# sapflow_v4.net
KiCad netlist of a schematic drawn in EAGLE
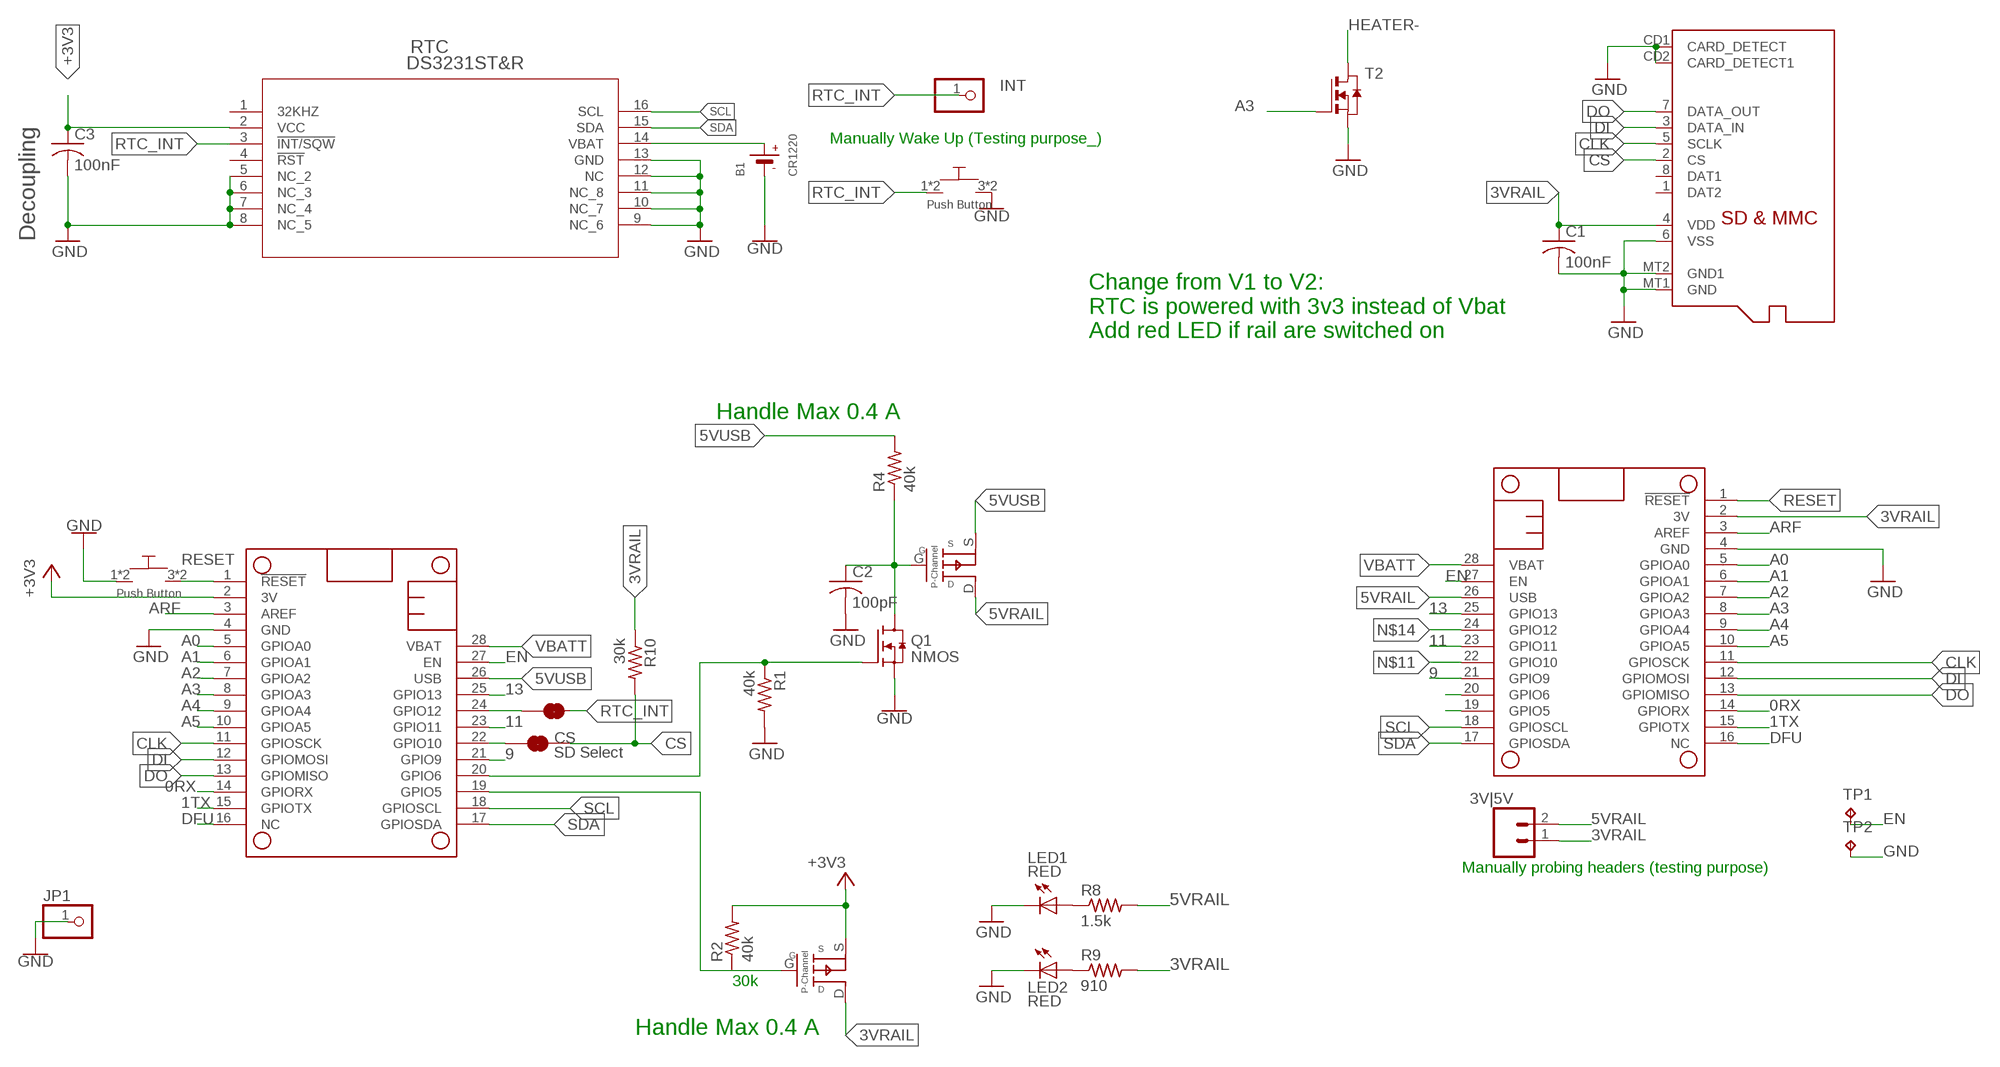
[diagram p0: schematic, sheet 1, part 1 of 2]
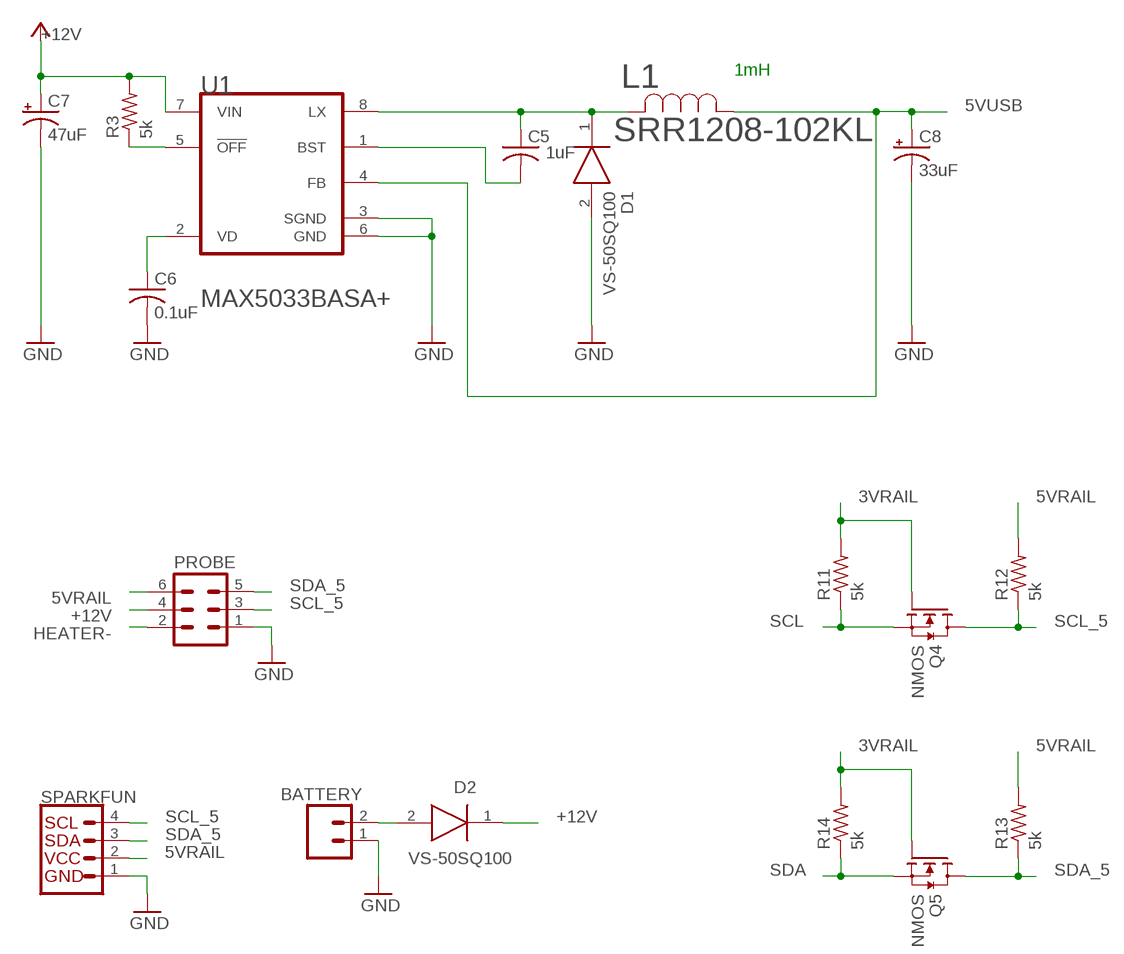
[diagram p1: schematic, sheet 1, part 2 of 2]

(export (version "E")
  (design (tool "Eeschema 10.0.6"))
  (components
    (comp (ref "3V|5V")
      (value "CONN_021X02_NO_SILK")
      (footprint "eagle-import:1X02_NO_SILK")
      (libsource (lib "eagle-import") (part "CONN_021X02_NO_SILK"))
    )
    (comp (ref "B1")
      (value "CR1220")
      (footprint "eagle-import:CR1220")
      (libsource (lib "eagle-import") (part "BATTERYCR1220_SMT"))
    )
    (comp (ref "BATTERY")
      (value "HIGHV-OUT")
      (footprint "eagle-import:1X02_NO_SILK")
      (libsource (lib "eagle-import") (part "CONN_021X02_NO_SILK"))
    )
    (comp (ref "C1")
      (value "100nF")
      (footprint "eagle-import:C0805")
      (libsource (lib "eagle-import") (part "C-USC0805"))
    )
    (comp (ref "C2")
      (value "100pF")
      (footprint "eagle-import:C0805")
      (libsource (lib "eagle-import") (part "resistor_348_C-USC0805"))
    )
    (comp (ref "C3")
      (value "100nF")
      (footprint "eagle-import:C0805")
      (libsource (lib "eagle-import") (part "C-USC0805"))
    )
    (comp (ref "C5")
      (value "1uF")
      (footprint "eagle-import:C0805")
      (libsource (lib "eagle-import") (part "rcl_334_C-USC0805"))
    )
    (comp (ref "C6")
      (value "0.1uF")
      (footprint "eagle-import:C0805")
      (libsource (lib "eagle-import") (part "rcl_334_C-USC0805"))
    )
    (comp (ref "C7")
      (value "47uF")
      (footprint "eagle-import:D_7343-31R")
      (libsource (lib "eagle-import") (part "CPOL-USD/7343-31R"))
    )
    (comp (ref "C8")
      (value "33uF")
      (footprint "eagle-import:D_7343-31R")
      (libsource (lib "eagle-import") (part "CPOL-USD/7343-31R"))
    )
    (comp (ref "CS")
      (value "SD Select")
      (footprint "eagle-import:SMT-JUMPER_2_NC_TRACE_SILK")
      (libsource (lib "eagle-import") (part "JUMPER-SMT_2_NC_TRACE_SILK"))
    )
    (comp (ref "D1")
      (value "VS-50SQ100")
      (footprint "eagle-import:DIOAD1405W86L465D235")
      (fields (field (name "MOUSER_PART_NUMBER") "844-50SQ100") (field (name "RS_PART_NUMBER") "5446041"))
      (libsource (lib "eagle-import") (part "VS-50SQ100"))
    )
    (comp (ref "D2")
      (value "VS-50SQ100")
      (footprint "eagle-import:DIOAD1405W86L465D235")
      (fields (field (name "MOUSER_PART_NUMBER") "844-50SQ100") (field (name "RS_PART_NUMBER") "5446041"))
      (libsource (lib "eagle-import") (part "VS-50SQ100"))
    )
    (comp (ref "INT")
      (value "PINHD-1X1CB")
      (footprint "eagle-import:1X01-CLEANBIG")
      (libsource (lib "eagle-import") (part "PINHD-1X1CB"))
    )
    (comp (ref "JP1")
      (value "PINHD-1X1CB")
      (footprint "eagle-import:1X01-CLEANBIG")
      (libsource (lib "eagle-import") (part "PINHD-1X1CB"))
    )
    (comp (ref "L1")
      (value "SRR1208-102KL")
      (footprint "eagle-import:IND_BOURNS_SRR1208")
      (libsource (lib "eagle-import") (part "SRR1208-102KL"))
    )
    (comp (ref "LED1")
      (value "RED")
      (footprint "eagle-import:CHIPLED_0805")
      (libsource (lib "eagle-import") (part "LEDCHIPLED_0805"))
    )
    (comp (ref "LED2")
      (value "RED")
      (footprint "eagle-import:CHIPLED_0805")
      (libsource (lib "eagle-import") (part "LEDCHIPLED_0805"))
    )
    (comp (ref "MICROSD")
      (value "MICROSD")
      (footprint "eagle-import:MICROSD")
      (libsource (lib "eagle-import") (part "MICROSD"))
    )
    (comp (ref "MS1")
      (value "FEATHERWING")
      (footprint "eagle-import:FEATHERWING")
      (libsource (lib "eagle-import") (part "powerboard_FEATHERWING"))
    )
    (comp (ref "MS2")
      (value "FEATHERWING")
      (footprint "eagle-import:FEATHERWING")
      (libsource (lib "eagle-import") (part "FEATHERWING"))
    )
    (comp (ref "PMOS1")
      (value "SSM3J3228R")
      (footprint "eagle-import:SOT-23-3")
      (libsource (lib "eagle-import") (part "SSM3J3228R"))
    )
    (comp (ref "PMOS2")
      (value "SSM3J3228R")
      (footprint "eagle-import:SOT-23-3")
      (libsource (lib "eagle-import") (part "SSM3J3228R"))
    )
    (comp (ref "PROBE")
      (value "MA03-2")
      (footprint "eagle-import:MA03-2")
      (libsource (lib "eagle-import") (part "MA03-2"))
    )
    (comp (ref "Q1")
      (value "NMOS")
      (footprint "eagle-import:SOT23-S")
      (libsource (lib "eagle-import") (part "NMOS"))
    )
    (comp (ref "Q4")
      (value "NMOS")
      (footprint "eagle-import:SOT23-S")
      (libsource (lib "eagle-import") (part "NMOS"))
    )
    (comp (ref "Q5")
      (value "NMOS")
      (footprint "eagle-import:SOT23-S")
      (libsource (lib "eagle-import") (part "NMOS"))
    )
    (comp (ref "R1")
      (value "40k")
      (footprint "eagle-import:R0805")
      (libsource (lib "eagle-import") (part "R-US_R0805"))
    )
    (comp (ref "R2")
      (value "40k")
      (footprint "eagle-import:R0805")
      (libsource (lib "eagle-import") (part "R-US_R0805"))
    )
    (comp (ref "R3")
      (value "5k")
      (footprint "eagle-import:R0805")
      (libsource (lib "eagle-import") (part "R-US_R0805"))
    )
    (comp (ref "R4")
      (value "40k")
      (footprint "eagle-import:R0805")
      (libsource (lib "eagle-import") (part "R-US_R0805"))
    )
    (comp (ref "R8")
      (value "1.5k")
      (footprint "eagle-import:R0805")
      (libsource (lib "eagle-import") (part "R-US_R0805"))
    )
    (comp (ref "R9")
      (value "910")
      (footprint "eagle-import:R0805")
      (libsource (lib "eagle-import") (part "R-US_R0805"))
    )
    (comp (ref "R10")
      (value "30k")
      (footprint "eagle-import:R0805")
      (libsource (lib "eagle-import") (part "R-US_R0805"))
    )
    (comp (ref "R11")
      (value "5k")
      (footprint "eagle-import:R0805")
      (libsource (lib "eagle-import") (part "R-US_R0805"))
    )
    (comp (ref "R12")
      (value "5k")
      (footprint "eagle-import:R0805")
      (libsource (lib "eagle-import") (part "R-US_R0805"))
    )
    (comp (ref "R13")
      (value "5k")
      (footprint "eagle-import:R0805")
      (libsource (lib "eagle-import") (part "R-US_R0805"))
    )
    (comp (ref "R14")
      (value "5k")
      (footprint "eagle-import:R0805")
      (libsource (lib "eagle-import") (part "R-US_R0805"))
    )
    (comp (ref "RTC")
      (value "DS3231ST&R")
      (footprint "eagle-import:21-0042B_16")
      (fields (field (name "MANUFACTURER_PART_NUMBER") "DS3231S#T&R"))
      (libsource (lib "eagle-import") (part "DS3231ST&R"))
    )
    (comp (ref "RTC_INT")
      (value "JUMPER-SMT_2_NC_TRACE_SILK")
      (footprint "eagle-import:SMT-JUMPER_2_NC_TRACE_SILK")
      (libsource (lib "eagle-import") (part "JUMPER-SMT_2_NC_TRACE_SILK"))
    )
    (comp (ref "SPARKFUN")
      (value "I2C_STANDARD_NO_SILK")
      (footprint "eagle-import:1X04_NO_SILK")
      (libsource (lib "eagle-import") (part "I2C_STANDARD_NO_SILK"))
    )
    (comp (ref "T2")
      (value "NMOSSOT223")
      (footprint "eagle-import:SOT223")
      (libsource (lib "eagle-import") (part "NMOSSOT223"))
    )
    (comp (ref "TP1")
      (value "TPTP16R")
      (footprint "eagle-import:TP16R")
      (libsource (lib "eagle-import") (part "TPTP16R"))
    )
    (comp (ref "TP2")
      (value "TPTP16R")
      (footprint "eagle-import:TP16R")
      (libsource (lib "eagle-import") (part "TPTP16R"))
    )
    (comp (ref "U$1")
      (value "PUSH_BUTTON")
      (footprint "eagle-import:PUSHBUTTON_SMD")
      (libsource (lib "eagle-import") (part "PUSH_BUTTON"))
    )
    (comp (ref "U$2")
      (value "PUSH_BUTTON")
      (footprint "eagle-import:PUSHBUTTON_SMD")
      (libsource (lib "eagle-import") (part "PUSH_BUTTON"))
    )
    (comp (ref "U1")
      (value "MAXIM_MAX5033BASA+MAXIM_MAX5033BASA+_0_1")
      (footprint "eagle-import:MAXIM_MAX5033BASA+_1")
      (fields (field (name "MF") "Maxim") (field (name "MPN") "MAX5033BASA+"))
      (libsource (lib "eagle-import") (part "MAXIM_MAX5033BASA+MAXIM_MAX5033BASA+_0_1"))
    )
  )
  (nets
    (net (code "1") (name "+3V3") (class "Default")
      (node (ref "C3") (pin "1") (pinfunction "1_1") (pintype "passive"))
      (node (ref "MS2") (pin "2") (pinfunction "3V_2") (pintype "power_in"))
      (node (ref "PMOS2") (pin "S") (pinfunction "S_S") (pintype "bidirectional"))
      (node (ref "R2") (pin "2") (pinfunction "2_2") (pintype "passive"))
      (node (ref "RTC") (pin "2") (pinfunction "VCC_2") (pintype "power_in"))
    )
    (net (code "2") (name "/0RX") (class "Default")
      (node (ref "MS1") (pin "14") (pinfunction "GPIORX_14") (pintype "bidirectional"))
      (node (ref "MS2") (pin "14") (pinfunction "GPIORX_14") (pintype "bidirectional"))
    )
    (net (code "3") (name "/1TX") (class "Default")
      (node (ref "MS1") (pin "15") (pinfunction "GPIOTX_15") (pintype "bidirectional"))
      (node (ref "MS2") (pin "15") (pinfunction "GPIOTX_15") (pintype "bidirectional"))
    )
    (net (code "4") (name "/9") (class "Default")
      (node (ref "MS1") (pin "21") (pinfunction "GPIO9_21") (pintype "bidirectional"))
      (node (ref "MS2") (pin "21") (pinfunction "GPIO9_21") (pintype "bidirectional"))
    )
    (net (code "5") (name "/11") (class "Default")
      (node (ref "MS1") (pin "23") (pinfunction "GPIO11_23") (pintype "bidirectional"))
      (node (ref "MS2") (pin "23") (pinfunction "GPIO11_23") (pintype "bidirectional"))
    )
    (net (code "6") (name "/13") (class "Default")
      (node (ref "MS1") (pin "25") (pinfunction "GPIO13_25") (pintype "bidirectional"))
      (node (ref "MS2") (pin "25") (pinfunction "GPIO13_25") (pintype "bidirectional"))
    )
    (net (code "7") (name "/A0") (class "Default")
      (node (ref "MS1") (pin "5") (pinfunction "GPIOA0_5") (pintype "bidirectional"))
      (node (ref "MS2") (pin "5") (pinfunction "GPIOA0_5") (pintype "bidirectional"))
    )
    (net (code "8") (name "/A1") (class "Default")
      (node (ref "MS1") (pin "6") (pinfunction "GPIOA1_6") (pintype "bidirectional"))
      (node (ref "MS2") (pin "6") (pinfunction "GPIOA1_6") (pintype "bidirectional"))
    )
    (net (code "9") (name "/A2") (class "Default")
      (node (ref "MS1") (pin "7") (pinfunction "GPIOA2_7") (pintype "bidirectional"))
      (node (ref "MS2") (pin "7") (pinfunction "GPIOA2_7") (pintype "bidirectional"))
    )
    (net (code "10") (name "/A3") (class "Default")
      (node (ref "MS1") (pin "8") (pinfunction "GPIOA3_8") (pintype "bidirectional"))
      (node (ref "MS2") (pin "8") (pinfunction "GPIOA3_8") (pintype "bidirectional"))
      (node (ref "T2") (pin "1") (pinfunction "G_1") (pintype "passive"))
    )
    (net (code "11") (name "/A4") (class "Default")
      (node (ref "MS1") (pin "9") (pinfunction "GPIOA4_9") (pintype "bidirectional"))
      (node (ref "MS2") (pin "9") (pinfunction "GPIOA4_9") (pintype "bidirectional"))
    )
    (net (code "12") (name "/A5") (class "Default")
      (node (ref "MS1") (pin "10") (pinfunction "GPIOA5_10") (pintype "bidirectional"))
      (node (ref "MS2") (pin "10") (pinfunction "GPIOA5_10") (pintype "bidirectional"))
    )
    (net (code "13") (name "/ARF") (class "Default")
      (node (ref "MS1") (pin "3") (pinfunction "AREF_3") (pintype "passive"))
      (node (ref "MS2") (pin "3") (pinfunction "AREF_3") (pintype "passive"))
    )
    (net (code "14") (name "/DFU") (class "Default")
      (node (ref "MS1") (pin "16") (pinfunction "NC_16") (pintype "passive"))
      (node (ref "MS2") (pin "16") (pinfunction "NC_16") (pintype "passive"))
    )
    (net (code "15") (name "/EN") (class "Default")
      (node (ref "MS1") (pin "27") (pinfunction "EN_27") (pintype "passive"))
      (node (ref "MS2") (pin "27") (pinfunction "EN_27") (pintype "passive"))
      (node (ref "TP1") (pin "TP") (pinfunction "TP_TP") (pintype "input"))
    )
    (net (code "16") (name "/HEATER-") (class "Default")
      (node (ref "PROBE") (pin "2") (pinfunction "2_2") (pintype "passive"))
      (node (ref "T2") (pin "2") (pinfunction "D_2") (pintype "passive"))
      (node (ref "T2") (pin "4") (pinfunction "D_4") (pintype "passive"))
    )
    (net (code "17") (name "/SCL_5") (class "Default")
      (node (ref "PROBE") (pin "3") (pinfunction "3_3") (pintype "passive"))
      (node (ref "Q4") (pin "3") (pinfunction "D_3") (pintype "passive"))
      (node (ref "R12") (pin "1") (pinfunction "1_1") (pintype "passive"))
      (node (ref "SPARKFUN") (pin "4") (pinfunction "SCL_4") (pintype "passive"))
    )
    (net (code "18") (name "/SDA_5") (class "Default")
      (node (ref "PROBE") (pin "5") (pinfunction "5_5") (pintype "passive"))
      (node (ref "Q5") (pin "3") (pinfunction "D_3") (pintype "passive"))
      (node (ref "R13") (pin "1") (pinfunction "1_1") (pintype "passive"))
      (node (ref "SPARKFUN") (pin "3") (pinfunction "SDA_3") (pintype "passive"))
    )
    (net (code "19") (name "3VRAIL") (class "Default")
      (node (ref "3V|5V") (pin "1") (pinfunction "1_1") (pintype "passive"))
      (node (ref "C1") (pin "1") (pinfunction "1_1") (pintype "passive"))
      (node (ref "MICROSD") (pin "4") (pinfunction "VDD_4") (pintype "power_in"))
      (node (ref "MS1") (pin "2") (pinfunction "3V_2") (pintype "power_in"))
      (node (ref "PMOS2") (pin "D") (pinfunction "D_D") (pintype "bidirectional"))
      (node (ref "Q4") (pin "1") (pinfunction "G_1") (pintype "passive"))
      (node (ref "Q5") (pin "1") (pinfunction "G_1") (pintype "passive"))
      (node (ref "R10") (pin "1") (pinfunction "1_1") (pintype "passive"))
      (node (ref "R11") (pin "2") (pinfunction "2_2") (pintype "passive"))
      (node (ref "R14") (pin "2") (pinfunction "2_2") (pintype "passive"))
      (node (ref "R9") (pin "2") (pinfunction "2_2") (pintype "passive"))
    )
    (net (code "20") (name "5VRAIL") (class "Default")
      (node (ref "3V|5V") (pin "2") (pinfunction "2_2") (pintype "passive"))
      (node (ref "MS1") (pin "26") (pinfunction "USB_26") (pintype "power_in"))
      (node (ref "PMOS1") (pin "D") (pinfunction "D_D") (pintype "bidirectional"))
      (node (ref "PROBE") (pin "6") (pinfunction "6_6") (pintype "passive"))
      (node (ref "R12") (pin "2") (pinfunction "2_2") (pintype "passive"))
      (node (ref "R13") (pin "2") (pinfunction "2_2") (pintype "passive"))
      (node (ref "R8") (pin "2") (pinfunction "2_2") (pintype "passive"))
      (node (ref "SPARKFUN") (pin "2") (pinfunction "VCC_2") (pintype "power_in"))
    )
    (net (code "21") (name "5VUSB") (class "Default")
      (node (ref "C8") (pin "+") (pinfunction "+_+") (pintype "passive"))
      (node (ref "L1") (pin "1") (pinfunction "1_1") (pintype "passive"))
      (node (ref "MS2") (pin "26") (pinfunction "USB_26") (pintype "power_in"))
      (node (ref "PMOS1") (pin "S") (pinfunction "S_S") (pintype "bidirectional"))
      (node (ref "R4") (pin "2") (pinfunction "2_2") (pintype "passive"))
      (node (ref "U1") (pin "4") (pinfunction "FB_4") (pintype "input"))
    )
    (net (code "22") (name "15V") (class "Default")
      (node (ref "C7") (pin "+") (pinfunction "+_+") (pintype "passive"))
      (node (ref "D2") (pin "1") (pinfunction "K_1") (pintype "bidirectional"))
      (node (ref "PROBE") (pin "4") (pinfunction "4_4") (pintype "passive"))
      (node (ref "R3") (pin "2") (pinfunction "2_2") (pintype "passive"))
      (node (ref "U1") (pin "7") (pinfunction "VIN_7") (pintype "power_in"))
    )
    (net (code "23") (name "CLK") (class "Default")
      (node (ref "MICROSD") (pin "5") (pinfunction "SCLK_5") (pintype "input"))
      (node (ref "MS1") (pin "11") (pinfunction "GPIOSCK_11") (pintype "bidirectional"))
      (node (ref "MS2") (pin "11") (pinfunction "GPIOSCK_11") (pintype "bidirectional"))
    )
    (net (code "24") (name "CS") (class "Default")
      (node (ref "CS") (pin "2") (pinfunction "2_2") (pintype "passive"))
      (node (ref "MICROSD") (pin "2") (pinfunction "CS_2") (pintype "input"))
      (node (ref "R10") (pin "2") (pinfunction "2_2") (pintype "passive"))
    )
    (net (code "25") (name "DI") (class "Default")
      (node (ref "MICROSD") (pin "3") (pinfunction "DATA_IN_3") (pintype "input"))
      (node (ref "MS1") (pin "12") (pinfunction "GPIOMOSI_12") (pintype "bidirectional"))
      (node (ref "MS2") (pin "12") (pinfunction "GPIOMOSI_12") (pintype "bidirectional"))
    )
    (net (code "26") (name "DO") (class "Default")
      (node (ref "MICROSD") (pin "7") (pinfunction "DATA_OUT_7") (pintype "output"))
      (node (ref "MS1") (pin "13") (pinfunction "GPIOMISO_13") (pintype "bidirectional"))
      (node (ref "MS2") (pin "13") (pinfunction "GPIOMISO_13") (pintype "bidirectional"))
    )
    (net (code "27") (name "GND") (class "Default")
      (node (ref "B1") (pin "-") (pinfunction "-_-") (pintype "passive"))
      (node (ref "BATTERY") (pin "1") (pinfunction "1_1") (pintype "passive"))
      (node (ref "C1") (pin "2") (pinfunction "2_2") (pintype "passive"))
      (node (ref "C2") (pin "2") (pinfunction "2_2") (pintype "passive"))
      (node (ref "C3") (pin "2") (pinfunction "2_2") (pintype "passive"))
      (node (ref "C6") (pin "2") (pinfunction "2_2") (pintype "passive"))
      (node (ref "C7") (pin "-") (pinfunction "-_-") (pintype "passive"))
      (node (ref "C8") (pin "-") (pinfunction "-_-") (pintype "passive"))
      (node (ref "D1") (pin "2") (pinfunction "A_2") (pintype "bidirectional"))
      (node (ref "JP1") (pin "1") (pinfunction "1_1") (pintype "passive"))
      (node (ref "LED1") (pin "C") (pinfunction "C_C") (pintype "passive"))
      (node (ref "LED2") (pin "C") (pinfunction "C_C") (pintype "passive"))
      (node (ref "MICROSD") (pin "6") (pinfunction "VSS_6") (pintype "power_in"))
      (node (ref "MICROSD") (pin "CD1") (pinfunction "CARD_DETECT_CD1") (pintype "passive"))
      (node (ref "MICROSD") (pin "CD2") (pinfunction "CARD_DETECT1_CD2") (pintype "passive"))
      (node (ref "MICROSD") (pin "MT1") (pinfunction "GND_MT1") (pintype "power_in"))
      (node (ref "MICROSD") (pin "MT2") (pinfunction "GND1_MT2") (pintype "power_in"))
      (node (ref "MS1") (pin "4") (pinfunction "GND_4") (pintype "power_in"))
      (node (ref "MS2") (pin "4") (pinfunction "GND_4") (pintype "power_in"))
      (node (ref "PROBE") (pin "1") (pinfunction "1_1") (pintype "passive"))
      (node (ref "Q1") (pin "2") (pinfunction "S_2") (pintype "passive"))
      (node (ref "R1") (pin "2") (pinfunction "2_2") (pintype "passive"))
      (node (ref "RTC") (pin "10") (pinfunction "NC_7_10") (pintype "passive"))
      (node (ref "RTC") (pin "11") (pinfunction "NC_8_11") (pintype "passive"))
      (node (ref "RTC") (pin "12") (pinfunction "NC_12") (pintype "passive"))
      (node (ref "RTC") (pin "13") (pinfunction "GND_13") (pintype "power_in"))
      (node (ref "RTC") (pin "5") (pinfunction "NC_2_5") (pintype "passive"))
      (node (ref "RTC") (pin "6") (pinfunction "NC_3_6") (pintype "passive"))
      (node (ref "RTC") (pin "7") (pinfunction "NC_4_7") (pintype "passive"))
      (node (ref "RTC") (pin "8") (pinfunction "NC_5_8") (pintype "passive"))
      (node (ref "RTC") (pin "9") (pinfunction "NC_6_9") (pintype "passive"))
      (node (ref "SPARKFUN") (pin "1") (pinfunction "GND_1") (pintype "power_in"))
      (node (ref "T2") (pin "3") (pinfunction "S_3") (pintype "passive"))
      (node (ref "TP2") (pin "TP") (pinfunction "TP_TP") (pintype "input"))
      (node (ref "U$1") (pin "1") (pinfunction "P$1_1") (pintype "bidirectional"))
      (node (ref "U$1") (pin "2") (pinfunction "P$1_2") (pintype "bidirectional"))
      (node (ref "U$2") (pin "3") (pinfunction "P$2_3") (pintype "bidirectional"))
      (node (ref "U$2") (pin "4") (pinfunction "P$2_4") (pintype "bidirectional"))
      (node (ref "U1") (pin "3") (pinfunction "SGND_3") (pintype "power_in"))
      (node (ref "U1") (pin "6") (pinfunction "GND_6") (pintype "power_in"))
    )
    (net (code "28") (name "N$11") (class "Default")
      (node (ref "CS") (pin "1") (pinfunction "1_1") (pintype "passive"))
      (node (ref "MS1") (pin "22") (pinfunction "GPIO10_22") (pintype "bidirectional"))
      (node (ref "MS2") (pin "22") (pinfunction "GPIO10_22") (pintype "bidirectional"))
    )
    (net (code "29") (name "N$14") (class "Default")
      (node (ref "MS1") (pin "24") (pinfunction "GPIO12_24") (pintype "bidirectional"))
      (node (ref "MS2") (pin "24") (pinfunction "GPIO12_24") (pintype "bidirectional"))
      (node (ref "RTC_INT") (pin "1") (pinfunction "1_1") (pintype "passive"))
    )
    (net (code "30") (name "Net-(B1-+)") (class "Default")
      (node (ref "B1") (pin "+$1") (pinfunction "+_+$1") (pintype "passive"))
      (node (ref "RTC") (pin "14") (pinfunction "VBAT_14") (pintype "power_in"))
    )
    (net (code "31") (name "Net-(D1-K)") (class "Default")
      (node (ref "C5") (pin "1") (pinfunction "1_1") (pintype "passive"))
      (node (ref "D1") (pin "1") (pinfunction "K_1") (pintype "bidirectional"))
      (node (ref "L1") (pin "2") (pinfunction "2_2") (pintype "passive"))
      (node (ref "U1") (pin "8") (pinfunction "LX_8") (pintype "passive"))
    )
    (net (code "32") (name "Net-(D2-A)") (class "Default")
      (node (ref "BATTERY") (pin "2") (pinfunction "2_2") (pintype "passive"))
      (node (ref "D2") (pin "2") (pinfunction "A_2") (pintype "bidirectional"))
    )
    (net (code "33") (name "Net-(LED1-PadA)") (class "Default")
      (node (ref "LED1") (pin "A") (pinfunction "A_A") (pintype "passive"))
      (node (ref "R8") (pin "1") (pinfunction "1_1") (pintype "passive"))
    )
    (net (code "34") (name "Net-(LED2-PadA)") (class "Default")
      (node (ref "LED2") (pin "A") (pinfunction "A_A") (pintype "passive"))
      (node (ref "R9") (pin "1") (pinfunction "1_1") (pintype "passive"))
    )
    (net (code "35") (name "Net-(MS2-GPIO5)") (class "Default")
      (node (ref "MS2") (pin "19") (pinfunction "GPIO5_19") (pintype "bidirectional"))
      (node (ref "PMOS2") (pin "G") (pinfunction "G_G") (pintype "bidirectional"))
      (node (ref "R2") (pin "1") (pinfunction "1_1") (pintype "passive"))
    )
    (net (code "36") (name "Net-(MS2-GPIO6)") (class "Default")
      (node (ref "MS2") (pin "20") (pinfunction "GPIO6_20") (pintype "bidirectional"))
      (node (ref "Q1") (pin "1") (pinfunction "G_1") (pintype "passive"))
      (node (ref "R1") (pin "1") (pinfunction "1_1") (pintype "passive"))
    )
    (net (code "37") (name "Net-(Q1-D)") (class "Default")
      (node (ref "C2") (pin "1") (pinfunction "1_1") (pintype "passive"))
      (node (ref "PMOS1") (pin "G") (pinfunction "G_G") (pintype "bidirectional"))
      (node (ref "Q1") (pin "3") (pinfunction "D_3") (pintype "passive"))
      (node (ref "R4") (pin "1") (pinfunction "1_1") (pintype "passive"))
    )
    (net (code "38") (name "Net-(U1-BST)") (class "Default")
      (node (ref "C5") (pin "2") (pinfunction "2_2") (pintype "passive"))
      (node (ref "U1") (pin "1") (pinfunction "BST_1") (pintype "passive"))
    )
    (net (code "39") (name "Net-(U1-VD)") (class "Default")
      (node (ref "C6") (pin "1") (pinfunction "1_1") (pintype "passive"))
      (node (ref "U1") (pin "2") (pinfunction "VD_2") (pintype "power_in"))
    )
    (net (code "40") (name "Net-(U1-~{OFF})") (class "Default")
      (node (ref "R3") (pin "1") (pinfunction "1_1") (pintype "passive"))
      (node (ref "U1") (pin "5") (pinfunction "~{OFF}_5") (pintype "input"))
    )
    (net (code "41") (name "RESET") (class "Default")
      (node (ref "MS1") (pin "1") (pinfunction "~{RESET}_1") (pintype "input"))
      (node (ref "MS2") (pin "1") (pinfunction "~{RESET}_1") (pintype "input"))
      (node (ref "U$1") (pin "3") (pinfunction "P$2_3") (pintype "bidirectional"))
      (node (ref "U$1") (pin "4") (pinfunction "P$2_4") (pintype "bidirectional"))
    )
    (net (code "42") (name "RTC_INT") (class "Default")
      (node (ref "INT") (pin "1") (pinfunction "1_1") (pintype "passive"))
      (node (ref "RTC") (pin "3") (pinfunction "~{INT/SQW}_3") (pintype "passive"))
      (node (ref "RTC_INT") (pin "2") (pinfunction "2_2") (pintype "passive"))
      (node (ref "U$2") (pin "1") (pinfunction "P$1_1") (pintype "bidirectional"))
      (node (ref "U$2") (pin "2") (pinfunction "P$1_2") (pintype "bidirectional"))
    )
    (net (code "43") (name "SCL") (class "Default")
      (node (ref "MS1") (pin "18") (pinfunction "GPIOSCL_18") (pintype "bidirectional"))
      (node (ref "MS2") (pin "18") (pinfunction "GPIOSCL_18") (pintype "bidirectional"))
      (node (ref "Q4") (pin "2") (pinfunction "S_2") (pintype "passive"))
      (node (ref "R11") (pin "1") (pinfunction "1_1") (pintype "passive"))
      (node (ref "RTC") (pin "16") (pinfunction "SCL_16") (pintype "passive"))
    )
    (net (code "44") (name "SDA") (class "Default")
      (node (ref "MS1") (pin "17") (pinfunction "GPIOSDA_17") (pintype "bidirectional"))
      (node (ref "MS2") (pin "17") (pinfunction "GPIOSDA_17") (pintype "bidirectional"))
      (node (ref "Q5") (pin "2") (pinfunction "S_2") (pintype "passive"))
      (node (ref "R14") (pin "1") (pinfunction "1_1") (pintype "passive"))
      (node (ref "RTC") (pin "15") (pinfunction "SDA_15") (pintype "passive"))
    )
    (net (code "45") (name "VBATT") (class "Default")
      (node (ref "MS1") (pin "28") (pinfunction "VBAT_28") (pintype "power_in"))
      (node (ref "MS2") (pin "28") (pinfunction "VBAT_28") (pintype "power_in"))
    )
    (net (code "46") (name "unconnected-(MICROSD-DAT1-Pad8)") (class "Default")
      (node (ref "MICROSD") (pin "8") (pinfunction "DAT1_8") (pintype "bidirectional"))
    )
    (net (code "47") (name "unconnected-(MICROSD-DAT2-Pad1)") (class "Default")
      (node (ref "MICROSD") (pin "1") (pinfunction "DAT2_1") (pintype "bidirectional"))
    )
    (net (code "48") (name "unconnected-(MS1-GPIO5-Pad19)") (class "Default")
      (node (ref "MS1") (pin "19") (pinfunction "GPIO5_19") (pintype "bidirectional"))
    )
    (net (code "49") (name "unconnected-(MS1-GPIO6-Pad20)") (class "Default")
      (node (ref "MS1") (pin "20") (pinfunction "GPIO6_20") (pintype "bidirectional"))
    )
    (net (code "50") (name "unconnected-(RTC-32KHZ-Pad1)") (class "Default")
      (node (ref "RTC") (pin "1") (pinfunction "32KHZ_1") (pintype "passive"))
    )
    (net (code "51") (name "unconnected-(RTC-~{RST}-Pad4)") (class "Default")
      (node (ref "RTC") (pin "4") (pinfunction "~{RST}_4") (pintype "passive"))
    )
  )
)
